# SectionA_Schematic.net
KiCad netlist of a schematic drawn in EAGLE
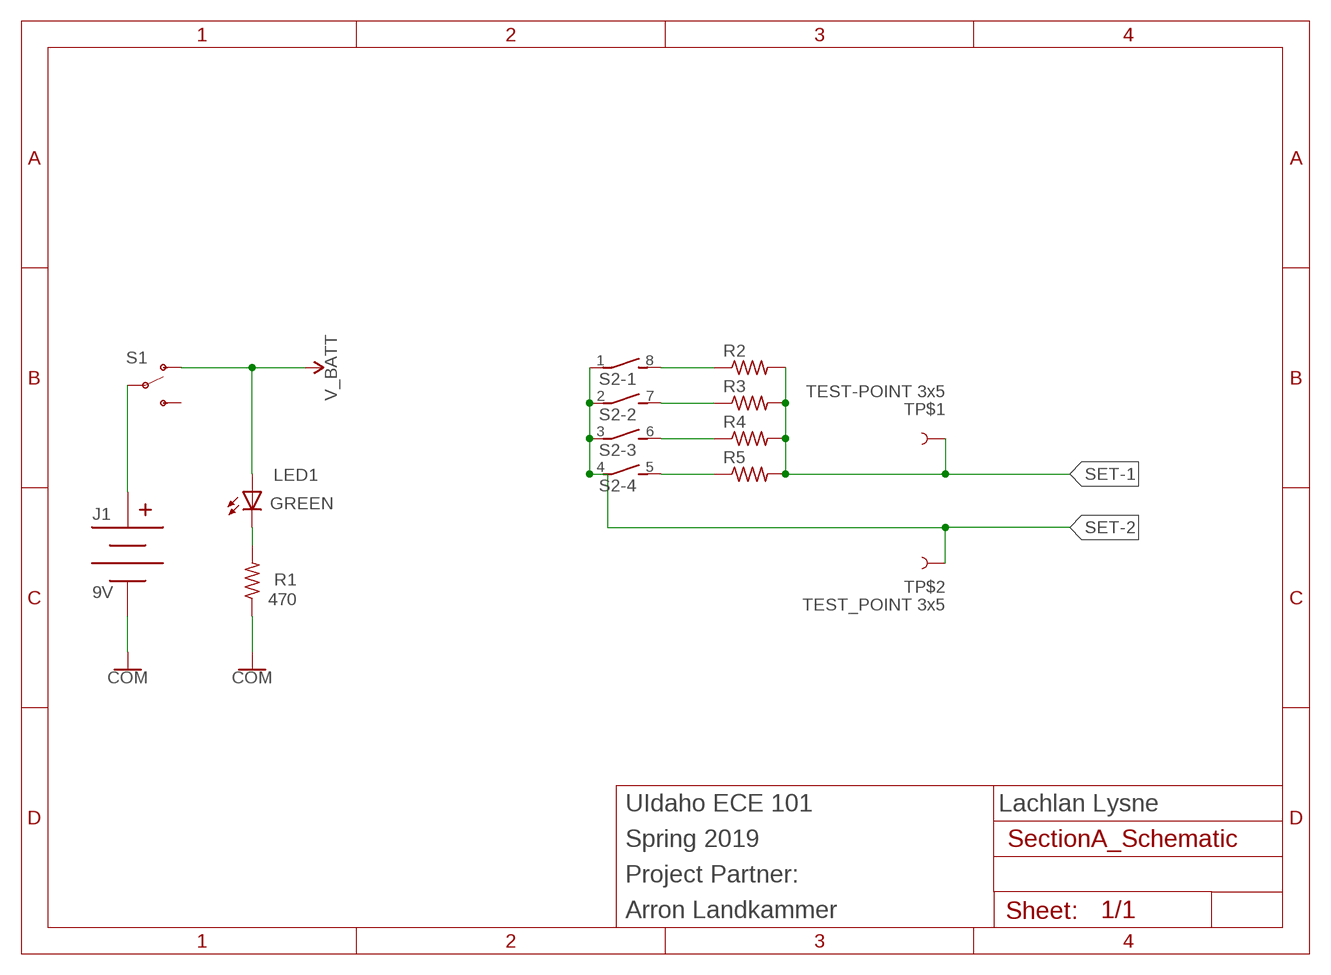
[diagram p0: schematic, sheet 1]

(export (version "E")
  (design (tool "Eeschema 10.0.6"))
  (components
    (comp (ref "J1")
      (value "9V")
      (footprint "eagle-import:SPARKFUN-CONNECTORS_BC9VPC")
      (libsource (lib "eagle-import") (part "SPARKFUN-CONNECTORS_BC9VPC"))
    )
    (comp (ref "LED1")
      (value "ADAFRUIT_LED5MM")
      (footprint "eagle-import:ADAFRUIT_LED5MM")
      (fields (field (name "COLOR") "GREEN"))
      (libsource (lib "eagle-import") (part "ADAFRUIT_LED5MM"))
    )
    (comp (ref "R1")
      (value "470")
      (footprint "eagle-import:ADAFRUIT_0207_10")
      (libsource (lib "eagle-import") (part "ADAFRUIT_R-US_0207/10"))
    )
    (comp (ref "R2")
      (value "ADAFRUIT_R-US_0207/10")
      (footprint "eagle-import:ADAFRUIT_0207_10")
      (libsource (lib "eagle-import") (part "ADAFRUIT_R-US_0207/10"))
    )
    (comp (ref "R3")
      (value "ADAFRUIT_R-US_0207/10")
      (footprint "eagle-import:ADAFRUIT_0207_10")
      (libsource (lib "eagle-import") (part "ADAFRUIT_R-US_0207/10"))
    )
    (comp (ref "R4")
      (value "ADAFRUIT_R-US_0207/10")
      (footprint "eagle-import:ADAFRUIT_0207_10")
      (libsource (lib "eagle-import") (part "ADAFRUIT_R-US_0207/10"))
    )
    (comp (ref "R5")
      (value "ADAFRUIT_R-US_0207/10")
      (footprint "eagle-import:ADAFRUIT_0207_10")
      (libsource (lib "eagle-import") (part "ADAFRUIT_R-US_0207/10"))
    )
    (comp (ref "S1")
      (value "SPARKFUN-SWITCHES_SWITCH-SPDT-PTH-11.6X4.0MM")
      (footprint "eagle-import:SPARKFUN-SWITCHES_SWITCH_SPDT_PTH_11.6X4.0MM")
      (libsource (lib "eagle-import") (part "SPARKFUN-SWITCHES_SWITCH-SPDT-PTH-11.6X4.0MM"))
    )
    (comp (ref "S2")
      (value "SWITCH-DIL_DIP04S")
      (footprint "eagle-import:SWITCH-DIL_DIP04S")
      (libsource (lib "eagle-import") (part "SWITCH-DIL_DIP04S"))
    )
    (comp (ref "TP$1")
      (value "TEST-POINT 3x5")
      (footprint "eagle-import:SPARKFUN-CONNECTORS_PAD.03X.05")
      (libsource (lib "eagle-import") (part "SPARKFUN-CONNECTORS_TEST-POINT3X5"))
    )
    (comp (ref "TP$2")
      (value "TEST_POINT 3x5")
      (footprint "eagle-import:SPARKFUN-CONNECTORS_PAD.03X.05")
      (libsource (lib "eagle-import") (part "SPARKFUN-CONNECTORS_TEST-POINT3X5"))
    )
  )
  (nets
    (net (code "1") (name "COM") (class "Default")
      (node (ref "J1") (pin "V-") (pinfunction "V-_V-") (pintype "bidirectional"))
      (node (ref "R1") (pin "1") (pinfunction "1_1") (pintype "passive"))
    )
    (net (code "2") (name "Net-(LED1-C)") (class "Default")
      (node (ref "LED1") (pin "K") (pinfunction "C_K") (pintype "passive"))
      (node (ref "R1") (pin "2") (pinfunction "2_2") (pintype "passive"))
    )
    (net (code "3") (name "Net-(S1-P)") (class "Default")
      (node (ref "J1") (pin "V+") (pinfunction "V+_V+") (pintype "bidirectional"))
      (node (ref "S1") (pin "2") (pinfunction "P_2") (pintype "passive"))
    )
    (net (code "4") (name "Net-(S2A-2)") (class "Default")
      (node (ref "R2") (pin "1") (pinfunction "1_1") (pintype "passive"))
      (node (ref "S2") (pin "8") (pinfunction "2_8") (pintype "passive"))
    )
    (net (code "5") (name "Net-(S2B-2)") (class "Default")
      (node (ref "R3") (pin "1") (pinfunction "1_1") (pintype "passive"))
      (node (ref "S2") (pin "7") (pinfunction "2_7") (pintype "passive"))
    )
    (net (code "6") (name "Net-(S2C-2)") (class "Default")
      (node (ref "R4") (pin "1") (pinfunction "1_1") (pintype "passive"))
      (node (ref "S2") (pin "6") (pinfunction "2_6") (pintype "passive"))
    )
    (net (code "7") (name "Net-(S2D-2)") (class "Default")
      (node (ref "R5") (pin "1") (pinfunction "1_1") (pintype "passive"))
      (node (ref "S2") (pin "5") (pinfunction "2_5") (pintype "passive"))
    )
    (net (code "8") (name "SET-1") (class "Default")
      (node (ref "R2") (pin "2") (pinfunction "2_2") (pintype "passive"))
      (node (ref "R3") (pin "2") (pinfunction "2_2") (pintype "passive"))
      (node (ref "R4") (pin "2") (pinfunction "2_2") (pintype "passive"))
      (node (ref "R5") (pin "2") (pinfunction "2_2") (pintype "passive"))
      (node (ref "TP$1") (pin "P$1") (pinfunction "1_P$1") (pintype "bidirectional"))
    )
    (net (code "9") (name "SET-2") (class "Default")
      (node (ref "S2") (pin "1") (pinfunction "1_1") (pintype "passive"))
      (node (ref "S2") (pin "2") (pinfunction "1_2") (pintype "passive"))
      (node (ref "S2") (pin "3") (pinfunction "1_3") (pintype "passive"))
      (node (ref "S2") (pin "4") (pinfunction "1_4") (pintype "passive"))
      (node (ref "TP$2") (pin "P$1") (pinfunction "1_P$1") (pintype "bidirectional"))
    )
    (net (code "10") (name "V_BATT") (class "Default")
      (node (ref "LED1") (pin "A") (pinfunction "A_A") (pintype "passive"))
      (node (ref "S1") (pin "1") (pinfunction "O_1") (pintype "passive"))
    )
    (net (code "11") (name "unconnected-(S1-S-Pad3)") (class "Default")
      (node (ref "S1") (pin "3") (pinfunction "S_3") (pintype "passive"))
    )
  )
)
